# dalibors-dock.net
KiCad netlist of a schematic drawn in Altium Designer
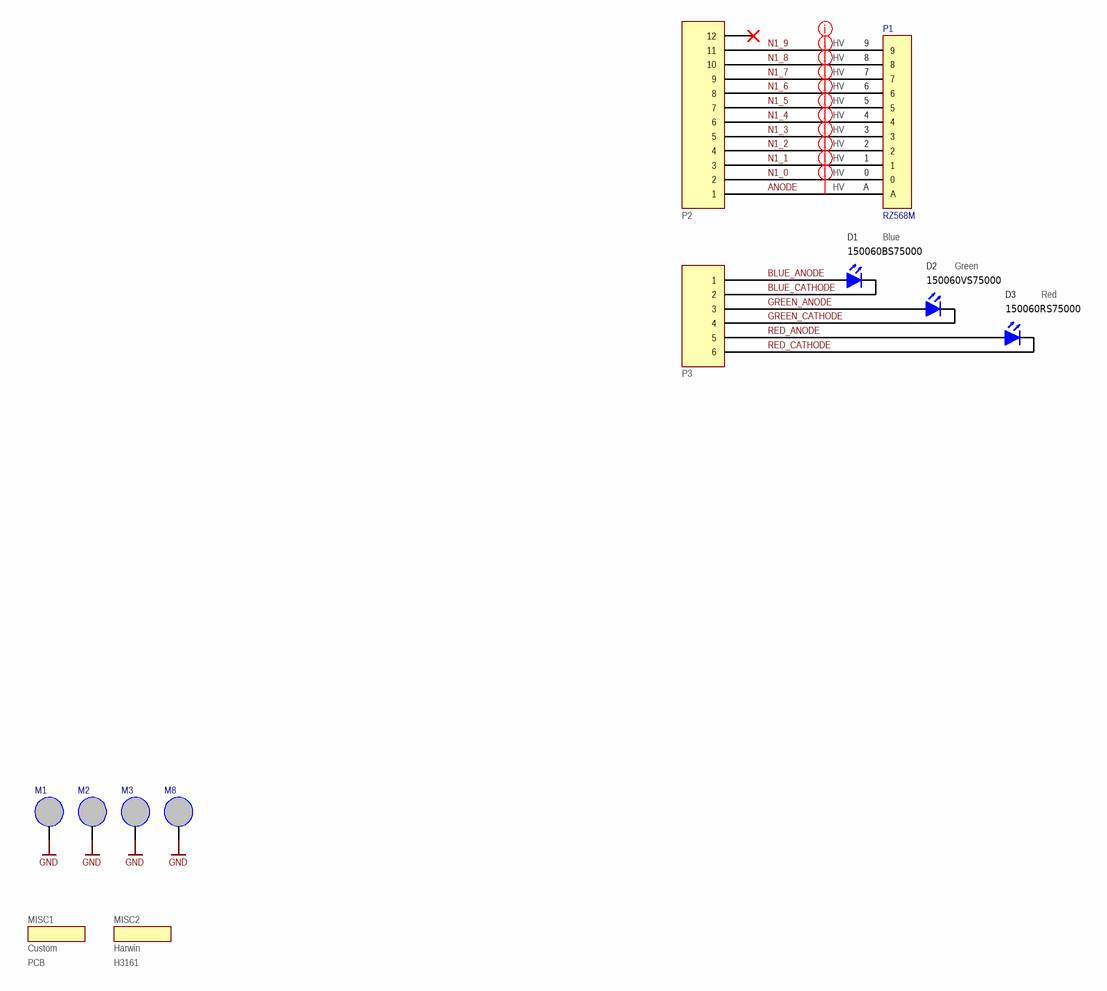
[diagram p0: dalibors-dock.SchDoc]

(export (version "E")
  (design (tool "Eeschema 10.0.6"))
  (components
    (comp (ref "D1")
      (value "150060BS75000‎")
      (footprint "0603_LED")
      (description "LED, SMT 0603, Color Blue")
      (fields (field (name "MANUFACTURER") "Wurth Electronics") (field (name "NOTE") "Blue"))
      (libsource (lib "generic") (part "LED0603GR"))
    )
    (comp (ref "D2")
      (value "150060VS75000‎")
      (footprint "0603_LED")
      (description "LED, SMT 0603, Color Green")
      (fields (field (name "MANUFACTURER") "Wurth Electronics") (field (name "NOTE") "Green"))
      (libsource (lib "generic") (part "LED0603GR"))
    )
    (comp (ref "D3")
      (value "150060RS75000‎")
      (footprint "0603_LED")
      (description "LED, SMT 0603, Color Red")
      (fields (field (name "MANUFACTURER") "Wurth Electronics") (field (name "NOTE") "Red"))
      (libsource (lib "generic") (part "LED0603Y"))
    )
    (comp (ref "M1") (value "MOUNT") (footprint "MOUNT1-4_20") (libsource (lib "generic") (part "MOUNT")))
    (comp (ref "M2") (value "MOUNT") (footprint "MOUNT1-4_20") (libsource (lib "generic") (part "MOUNT")))
    (comp (ref "M3") (value "MOUNT") (footprint "MOUNT1-4_20") (libsource (lib "generic") (part "MOUNT")))
    (comp (ref "M8") (value "MOUNT") (footprint "MOUNT1-4_20") (libsource (lib "generic") (part "MOUNT")))
    (comp (ref "MISC1")
      (value "PCB")
      (fields (field (name "MANUFACTURER") "Custom"))
      (libsource (lib "harwin") (part "M50-1900005"))
    )
    (comp (ref "MISC2")
      (value "H3161")
      (description "Pin Receptacle")
      (fields (field (name "MANUFACTURER") "Harwin"))
      (libsource (lib "harwin") (part "M50-1900005"))
    )
    (comp (ref "P1")
      (value "RZ568M")
      (footprint "RZ568M")
      (description "Nixie Tube Socket")
      (fields (field (name "MANUFACTURER") "Glow Tube Research"))
      (libsource (lib "sigsub") (part "RZ568M"))
    )
    (comp (ref "P2")
      (value "S12B-XH-A")
      (footprint "jst:S12B-XH-A")
      (description "2.5mm pitch right angle 12-position")
      (fields (field (name "MANUFACTURER") "JST"))
      (libsource (lib "jst") (part "S12B-XH-A"))
    )
    (comp (ref "P3")
      (value "S6B-ZR")
      (footprint "jst:S6B-ZR")
      (description "1.5mm pitch right angle 6-position")
      (fields (field (name "MANUFACTURER") "JST"))
      (libsource (lib "jst") (part "S6B-ZR"))
    )
  )
  (nets
    (net (code "1") (name "/ANODE") (class "Default")
      (node (ref "P1") (pin "A") (pinfunction "A_A") (pintype "passive"))
      (node (ref "P2") (pin "1") (pinfunction "1_1") (pintype "passive"))
    )
    (net (code "2") (name "/BLUE_ANODE") (class "Default")
      (node (ref "D1") (pin "1") (pinfunction "A_1") (pintype "passive"))
      (node (ref "P3") (pin "1") (pinfunction "1_1") (pintype "passive"))
    )
    (net (code "3") (name "/BLUE_CATHODE") (class "Default")
      (node (ref "D1") (pin "2") (pinfunction "K_2") (pintype "passive"))
      (node (ref "P3") (pin "2") (pinfunction "2_2") (pintype "passive"))
    )
    (net (code "4") (name "/GREEN_ANODE") (class "Default")
      (node (ref "D2") (pin "1") (pinfunction "A_1") (pintype "passive"))
      (node (ref "P3") (pin "3") (pinfunction "3_3") (pintype "passive"))
    )
    (net (code "5") (name "/GREEN_CATHODE") (class "Default")
      (node (ref "D2") (pin "2") (pinfunction "K_2") (pintype "passive"))
      (node (ref "P3") (pin "4") (pinfunction "4_4") (pintype "passive"))
    )
    (net (code "6") (name "/N1_0") (class "Default")
      (node (ref "P1") (pin "0") (pinfunction "0_0") (pintype "passive"))
      (node (ref "P2") (pin "2") (pinfunction "2_2") (pintype "passive"))
    )
    (net (code "7") (name "/N1_1") (class "Default")
      (node (ref "P1") (pin "1") (pinfunction "1_1") (pintype "passive"))
      (node (ref "P2") (pin "3") (pinfunction "3_3") (pintype "passive"))
    )
    (net (code "8") (name "/N1_2") (class "Default")
      (node (ref "P1") (pin "2") (pinfunction "2_2") (pintype "passive"))
      (node (ref "P2") (pin "4") (pinfunction "4_4") (pintype "passive"))
    )
    (net (code "9") (name "/N1_3") (class "Default")
      (node (ref "P1") (pin "3") (pinfunction "3_3") (pintype "passive"))
      (node (ref "P2") (pin "5") (pinfunction "5_5") (pintype "passive"))
    )
    (net (code "10") (name "/N1_4") (class "Default")
      (node (ref "P1") (pin "4") (pinfunction "4_4") (pintype "passive"))
      (node (ref "P2") (pin "6") (pinfunction "6_6") (pintype "passive"))
    )
    (net (code "11") (name "/N1_5") (class "Default")
      (node (ref "P1") (pin "5") (pinfunction "5_5") (pintype "passive"))
      (node (ref "P2") (pin "7") (pinfunction "7_7") (pintype "passive"))
    )
    (net (code "12") (name "/N1_6") (class "Default")
      (node (ref "P1") (pin "6") (pinfunction "6_6") (pintype "passive"))
      (node (ref "P2") (pin "8") (pinfunction "8_8") (pintype "passive"))
    )
    (net (code "13") (name "/N1_7") (class "Default")
      (node (ref "P1") (pin "7") (pinfunction "7_7") (pintype "passive"))
      (node (ref "P2") (pin "9") (pinfunction "9_9") (pintype "passive"))
    )
    (net (code "14") (name "/N1_8") (class "Default")
      (node (ref "P1") (pin "8") (pinfunction "8_8") (pintype "passive"))
      (node (ref "P2") (pin "10") (pinfunction "10_10") (pintype "passive"))
    )
    (net (code "15") (name "/N1_9") (class "Default")
      (node (ref "P1") (pin "9") (pinfunction "9_9") (pintype "passive"))
      (node (ref "P2") (pin "11") (pinfunction "11_11") (pintype "passive"))
    )
    (net (code "16") (name "/RED_ANODE") (class "Default")
      (node (ref "D3") (pin "1") (pinfunction "A_1") (pintype "passive"))
      (node (ref "P3") (pin "5") (pinfunction "5_5") (pintype "passive"))
    )
    (net (code "17") (name "/RED_CATHODE") (class "Default")
      (node (ref "D3") (pin "2") (pinfunction "K_2") (pintype "passive"))
      (node (ref "P3") (pin "6") (pinfunction "6_6") (pintype "passive"))
    )
    (net (code "18") (name "GND") (class "Default")
      (node (ref "M1") (pin "1") (pinfunction "MNT_1") (pintype "passive"))
      (node (ref "M2") (pin "1") (pinfunction "MNT_1") (pintype "passive"))
      (node (ref "M3") (pin "1") (pinfunction "MNT_1") (pintype "passive"))
      (node (ref "M8") (pin "1") (pinfunction "MNT_1") (pintype "passive"))
    )
    (net (code "19") (name "unconnected-(P2-Pad12)") (class "Default")
      (node (ref "P2") (pin "12") (pinfunction "12_12") (pintype "passive+no_connect"))
    )
  )
)
